# ScanQR_ESP32_sch.net
KiCad netlist of a schematic drawn in Altium Designer
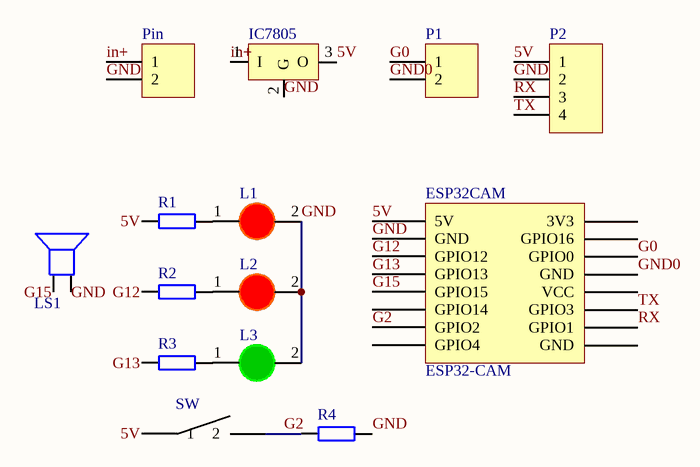
[diagram p0: ScanQR_ESP32_sch.SchDoc]

(export (version "E")
  (design (tool "Eeschema 10.0.6"))
  (components
    (comp (ref "ESP32CAM")
      (value "ESP32-CAM")
      (footprint "ESP32-CAM")
      (libsource (lib "Library_AnTran") (part "ESP32-CAM"))
    )
    (comp (ref "IC7805")
      (value "LM78xx")
      (footprint "TO220-123")
      (description "Positive Voltage Regulator")
      (fields (field (name "PUBLISHER") "Altium Limited"))
      (libsource (lib "lib_Dl") (part "LM78xx"))
    )
    (comp (ref "L1")
      (value "LED 5mm")
      (footprint "LED-5MM-RED")
      (description "Cắm")
      (libsource (lib "Altium_Lib_by_KhueNguyenCreator") (part "LED 5mm Do"))
    )
    (comp (ref "L2")
      (value "LED 5mm")
      (footprint "LED-5MM-RED")
      (description "Cắm")
      (libsource (lib "Altium_Lib_by_KhueNguyenCreator") (part "LED 5mm Do"))
    )
    (comp (ref "L3")
      (value "LED 5mm")
      (footprint "LED-5MM-Green")
      (description "Cắm")
      (libsource (lib "Altium_Lib_by_KhueNguyenCreator") (part "LED 5mm Xanh La"))
    )
    (comp (ref "LS1")
      (value "Coi Chip Speaker")
      (footprint "Coi Chip Speacker")
      (description "Còi chip")
      (libsource (lib "Altium_Lib_by_KhueNguyenCreator") (part "Coi Chip Speaker"))
    )
    (comp (ref "P1")
      (value "Header 2x1")
      (footprint "HDR1X2")
      (description "Header, 2-Pin, pitch 2.54mm")
      (libsource (lib "BYTECH_HW_LIB_2019") (part "Header 2x1"))
    )
    (comp (ref "P2")
      (value "Header 4P")
      (footprint "HDR1X4")
      (description "Header, 4 Pin Pitch 2.54mm")
      (fields (field (name "MPN") "S1012EC-40-ND"))
      (libsource (lib "BYTECH_HW_LIB_2019") (part "Header 4x1"))
    )
    (comp (ref "Pin")
      (value "Header 2x1")
      (footprint "HDR1X2")
      (description "Header, 2-Pin, pitch 2.54mm")
      (libsource (lib "BYTECH_HW_LIB_2019") (part "Header 2x1"))
    )
    (comp (ref "R1")
      (value "0.11R")
      (footprint "tro vach 1/4w")
      (description "Cắm")
      (libsource (lib "Altium_Lib_by_KhueNguyenCreator") (part "Tro Vach 1/4W 5% 0.11R"))
    )
    (comp (ref "R2")
      (value "0.11R")
      (footprint "tro vach 1/4w")
      (description "Cắm")
      (libsource (lib "Altium_Lib_by_KhueNguyenCreator") (part "Tro Vach 1/4W 5% 0.11R"))
    )
    (comp (ref "R3")
      (value "0.11R")
      (footprint "tro vach 1/4w")
      (description "Cắm")
      (libsource (lib "Altium_Lib_by_KhueNguyenCreator") (part "Tro Vach 1/4W 5% 0.11R"))
    )
    (comp (ref "R4")
      (value "0.11R")
      (footprint "tro vach 1/4w")
      (description "Cắm")
      (libsource (lib "Altium_Lib_by_KhueNguyenCreator") (part "Tro Vach 1/4W 5% 0.11R"))
    )
    (comp (ref "SW")
      (value "Switch 2pins 6x6x5")
      (footprint "Switch 2pins 6x6x5")
      (libsource (lib "Library_AnTran") (part "Switch 2pins 6x6x5"))
    )
  )
  (nets
    (net (code "1") (name "/5V") (class "Default")
      (node (ref "ESP32CAM") (pin "1") (pinfunction "5V_1") (pintype "passive"))
      (node (ref "IC7805") (pin "3") (pinfunction "O_3") (pintype "power_in"))
      (node (ref "P2") (pin "1") (pinfunction "1_1") (pintype "passive"))
      (node (ref "R1") (pin "1") (pinfunction "1_1") (pintype "passive"))
      (node (ref "SW") (pin "1") (pinfunction "1_1") (pintype "passive"))
    )
    (net (code "2") (name "/G0") (class "Default")
      (node (ref "ESP32CAM") (pin "14") (pinfunction "GPIO0_14") (pintype "passive"))
      (node (ref "P1") (pin "1") (pinfunction "1_1") (pintype "passive"))
    )
    (net (code "3") (name "/G2") (class "Default")
      (node (ref "ESP32CAM") (pin "7") (pinfunction "GPIO2_7") (pintype "passive"))
      (node (ref "R4") (pin "1") (pinfunction "1_1") (pintype "passive"))
      (node (ref "SW") (pin "2") (pinfunction "2_2") (pintype "passive"))
    )
    (net (code "4") (name "/G12") (class "Default")
      (node (ref "ESP32CAM") (pin "3") (pinfunction "GPIO12_3") (pintype "passive"))
      (node (ref "R2") (pin "1") (pinfunction "1_1") (pintype "passive"))
    )
    (net (code "5") (name "/G13") (class "Default")
      (node (ref "ESP32CAM") (pin "4") (pinfunction "GPIO13_4") (pintype "passive"))
      (node (ref "R3") (pin "1") (pinfunction "1_1") (pintype "passive"))
    )
    (net (code "6") (name "/G15") (class "Default")
      (node (ref "ESP32CAM") (pin "5") (pinfunction "GPIO15_5") (pintype "passive"))
      (node (ref "LS1") (pin "1") (pinfunction "1_1") (pintype "passive"))
    )
    (net (code "7") (name "/GND") (class "Default")
      (node (ref "ESP32CAM") (pin "2") (pinfunction "GND_2") (pintype "passive"))
      (node (ref "IC7805") (pin "2") (pinfunction "G_2") (pintype "power_in"))
      (node (ref "L1") (pin "2") (pinfunction "K_2") (pintype "passive"))
      (node (ref "L2") (pin "2") (pinfunction "K_2") (pintype "passive"))
      (node (ref "L3") (pin "2") (pinfunction "K_2") (pintype "passive"))
      (node (ref "LS1") (pin "2") (pinfunction "2_2") (pintype "passive"))
      (node (ref "P2") (pin "2") (pinfunction "2_2") (pintype "passive"))
      (node (ref "Pin") (pin "2") (pinfunction "2_2") (pintype "passive"))
      (node (ref "R4") (pin "2") (pinfunction "2_2") (pintype "passive"))
    )
    (net (code "8") (name "/GND0") (class "Default")
      (node (ref "ESP32CAM") (pin "13") (pinfunction "GND_13") (pintype "passive"))
      (node (ref "P1") (pin "2") (pinfunction "2_2") (pintype "passive"))
    )
    (net (code "9") (name "/RX") (class "Default")
      (node (ref "ESP32CAM") (pin "10") (pinfunction "GPIO1_10") (pintype "passive"))
      (node (ref "P2") (pin "3") (pinfunction "3_3") (pintype "passive"))
    )
    (net (code "10") (name "/TX") (class "Default")
      (node (ref "ESP32CAM") (pin "11") (pinfunction "GPIO3_11") (pintype "passive"))
      (node (ref "P2") (pin "4") (pinfunction "4_4") (pintype "passive"))
    )
    (net (code "11") (name "/in+") (class "Default")
      (node (ref "IC7805") (pin "1") (pinfunction "I_1") (pintype "power_in"))
      (node (ref "Pin") (pin "1") (pinfunction "1_1") (pintype "passive"))
    )
    (net (code "12") (name "Net-(L1-A)") (class "Default")
      (node (ref "L1") (pin "1") (pinfunction "A_1") (pintype "passive"))
      (node (ref "R1") (pin "2") (pinfunction "2_2") (pintype "passive"))
    )
    (net (code "13") (name "Net-(L2-A)") (class "Default")
      (node (ref "L2") (pin "1") (pinfunction "A_1") (pintype "passive"))
      (node (ref "R2") (pin "2") (pinfunction "2_2") (pintype "passive"))
    )
    (net (code "14") (name "Net-(L3-A)") (class "Default")
      (node (ref "L3") (pin "1") (pinfunction "A_1") (pintype "passive"))
      (node (ref "R3") (pin "2") (pinfunction "2_2") (pintype "passive"))
    )
    (net (code "15") (name "unconnected-(ESP32CAM-3V3-Pad16)") (class "Default")
      (node (ref "ESP32CAM") (pin "16") (pinfunction "3V3_16") (pintype "passive"))
    )
    (net (code "16") (name "unconnected-(ESP32CAM-GND-Pad9)") (class "Default")
      (node (ref "ESP32CAM") (pin "9") (pinfunction "GND_9") (pintype "passive"))
    )
    (net (code "17") (name "unconnected-(ESP32CAM-GPIO4-Pad8)") (class "Default")
      (node (ref "ESP32CAM") (pin "8") (pinfunction "GPIO4_8") (pintype "passive"))
    )
    (net (code "18") (name "unconnected-(ESP32CAM-GPIO14-Pad6)") (class "Default")
      (node (ref "ESP32CAM") (pin "6") (pinfunction "GPIO14_6") (pintype "passive"))
    )
    (net (code "19") (name "unconnected-(ESP32CAM-GPIO16-Pad15)") (class "Default")
      (node (ref "ESP32CAM") (pin "15") (pinfunction "GPIO16_15") (pintype "passive"))
    )
    (net (code "20") (name "unconnected-(ESP32CAM-VCC-Pad12)") (class "Default")
      (node (ref "ESP32CAM") (pin "12") (pinfunction "VCC_12") (pintype "passive"))
    )
  )
)
